# Voltage_Measurement.net
KiCad netlist of a schematic drawn in Altium Designer
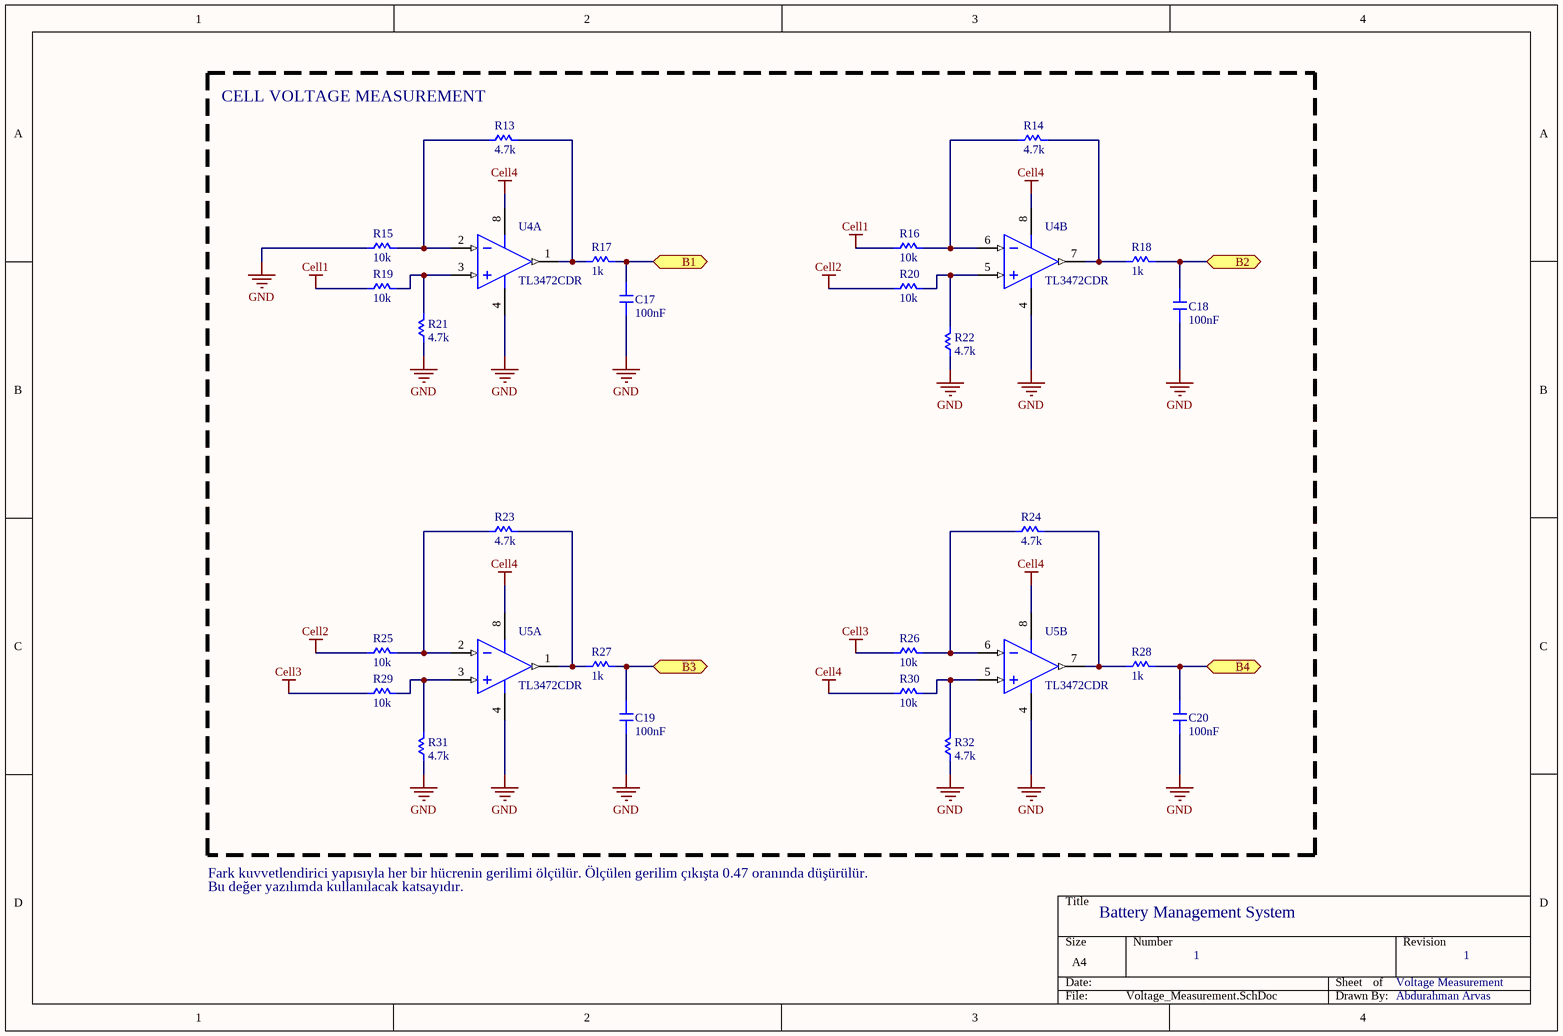
[diagram p0: Voltage_Measurement.SchDoc]

(export (version "E")
  (design (tool "Eeschema 10.0.6"))
  (components
    (comp (ref "C17")
      (value "100nF")
      (footprint "C0805")
      (libsource (lib "Arvas_AltiumSCH") (part "SMD_Capacitor"))
    )
    (comp (ref "C18")
      (value "100nF")
      (footprint "C0805")
      (libsource (lib "Arvas_AltiumSCH") (part "SMD_Capacitor"))
    )
    (comp (ref "C19")
      (value "100nF")
      (footprint "C0805")
      (libsource (lib "Arvas_AltiumSCH") (part "SMD_Capacitor"))
    )
    (comp (ref "C20")
      (value "100nF")
      (footprint "C0805")
      (libsource (lib "Arvas_AltiumSCH") (part "SMD_Capacitor"))
    )
    (comp (ref "R13")
      (value "4.7k")
      (footprint "R0805")
      (description "SMD Chip Resistor")
      (libsource (lib "Arvas_AltiumSCH") (part "SMD Resistor"))
    )
    (comp (ref "R14")
      (value "4.7k")
      (footprint "R0805")
      (description "SMD Chip Resistor")
      (libsource (lib "Arvas_AltiumSCH") (part "SMD Resistor"))
    )
    (comp (ref "R15")
      (value "10k")
      (footprint "R0805")
      (description "SMD Chip Resistor")
      (libsource (lib "Arvas_AltiumSCH") (part "SMD Resistor"))
    )
    (comp (ref "R16")
      (value "10k")
      (footprint "R0805")
      (description "SMD Chip Resistor")
      (libsource (lib "Arvas_AltiumSCH") (part "SMD Resistor"))
    )
    (comp (ref "R17")
      (value "1k")
      (footprint "R0805")
      (description "SMD Chip Resistor")
      (libsource (lib "Arvas_AltiumSCH") (part "SMD Resistor"))
    )
    (comp (ref "R18")
      (value "1k")
      (footprint "R0805")
      (description "SMD Chip Resistor")
      (libsource (lib "Arvas_AltiumSCH") (part "SMD Resistor"))
    )
    (comp (ref "R19")
      (value "10k")
      (footprint "R0805")
      (description "SMD Chip Resistor")
      (libsource (lib "Arvas_AltiumSCH") (part "SMD Resistor"))
    )
    (comp (ref "R20")
      (value "10k")
      (footprint "R0805")
      (description "SMD Chip Resistor")
      (libsource (lib "Arvas_AltiumSCH") (part "SMD Resistor"))
    )
    (comp (ref "R21")
      (value "4.7k")
      (footprint "R0805")
      (description "SMD Chip Resistor")
      (libsource (lib "Arvas_AltiumSCH") (part "SMD Resistor"))
    )
    (comp (ref "R22")
      (value "4.7k")
      (footprint "R0805")
      (description "SMD Chip Resistor")
      (libsource (lib "Arvas_AltiumSCH") (part "SMD Resistor"))
    )
    (comp (ref "R23")
      (value "4.7k")
      (footprint "R0805")
      (description "SMD Chip Resistor")
      (libsource (lib "Arvas_AltiumSCH") (part "SMD Resistor"))
    )
    (comp (ref "R24")
      (value "4.7k")
      (footprint "R0805")
      (description "SMD Chip Resistor")
      (libsource (lib "Arvas_AltiumSCH") (part "SMD Resistor"))
    )
    (comp (ref "R25")
      (value "10k")
      (footprint "R0805")
      (description "SMD Chip Resistor")
      (libsource (lib "Arvas_AltiumSCH") (part "SMD Resistor"))
    )
    (comp (ref "R26")
      (value "10k")
      (footprint "R0805")
      (description "SMD Chip Resistor")
      (libsource (lib "Arvas_AltiumSCH") (part "SMD Resistor"))
    )
    (comp (ref "R27")
      (value "1k")
      (footprint "R0805")
      (description "SMD Chip Resistor")
      (libsource (lib "Arvas_AltiumSCH") (part "SMD Resistor"))
    )
    (comp (ref "R28")
      (value "1k")
      (footprint "R0805")
      (description "SMD Chip Resistor")
      (libsource (lib "Arvas_AltiumSCH") (part "SMD Resistor"))
    )
    (comp (ref "R29")
      (value "10k")
      (footprint "R0805")
      (description "SMD Chip Resistor")
      (libsource (lib "Arvas_AltiumSCH") (part "SMD Resistor"))
    )
    (comp (ref "R30")
      (value "10k")
      (footprint "R0805")
      (description "SMD Chip Resistor")
      (libsource (lib "Arvas_AltiumSCH") (part "SMD Resistor"))
    )
    (comp (ref "R31")
      (value "4.7k")
      (footprint "R0805")
      (description "SMD Chip Resistor")
      (libsource (lib "Arvas_AltiumSCH") (part "SMD Resistor"))
    )
    (comp (ref "R32")
      (value "4.7k")
      (footprint "R0805")
      (description "SMD Chip Resistor")
      (libsource (lib "Arvas_AltiumSCH") (part "SMD Resistor"))
    )
    (comp (ref "U4")
      (value "TL3472CDR")
      (footprint "D0008A_L")
      (fields (field (name "MANUFACTURER") "Texas Instruments"))
      (libsource (lib "Altium Content Vault") (part "TI-TL3472-XX-X8"))
    )
    (comp (ref "U5")
      (value "TL3472CDR")
      (footprint "D0008A_L")
      (fields (field (name "MANUFACTURER") "Texas Instruments"))
      (libsource (lib "Altium Content Vault") (part "TI-TL3472-XX-X8"))
    )
  )
  (nets
    (net (code "1") (name "/B1") (class "Default")
      (node (ref "C17") (pin "2") (pinfunction "2_2") (pintype "passive"))
      (node (ref "R17") (pin "2") (pinfunction "2_2") (pintype "passive"))
    )
    (net (code "2") (name "/B2") (class "Default")
      (node (ref "C18") (pin "2") (pinfunction "2_2") (pintype "passive"))
      (node (ref "R18") (pin "2") (pinfunction "2_2") (pintype "passive"))
    )
    (net (code "3") (name "/B3") (class "Default")
      (node (ref "C19") (pin "2") (pinfunction "2_2") (pintype "passive"))
      (node (ref "R27") (pin "2") (pinfunction "2_2") (pintype "passive"))
    )
    (net (code "4") (name "/B4") (class "Default")
      (node (ref "C20") (pin "2") (pinfunction "2_2") (pintype "passive"))
      (node (ref "R28") (pin "2") (pinfunction "2_2") (pintype "passive"))
    )
    (net (code "5") (name "Cell1") (class "Default")
      (node (ref "R16") (pin "1") (pinfunction "1_1") (pintype "passive"))
      (node (ref "R19") (pin "1") (pinfunction "1_1") (pintype "passive"))
    )
    (net (code "6") (name "Cell2") (class "Default")
      (node (ref "R20") (pin "1") (pinfunction "1_1") (pintype "passive"))
      (node (ref "R25") (pin "1") (pinfunction "1_1") (pintype "passive"))
    )
    (net (code "7") (name "Cell3") (class "Default")
      (node (ref "R26") (pin "1") (pinfunction "1_1") (pintype "passive"))
      (node (ref "R29") (pin "1") (pinfunction "1_1") (pintype "passive"))
    )
    (net (code "8") (name "Cell4") (class "Default")
      (node (ref "R30") (pin "1") (pinfunction "1_1") (pintype "passive"))
      (node (ref "U4") (pin "8") (pinfunction "VCC+_8") (pintype "power_in"))
      (node (ref "U5") (pin "8") (pinfunction "VCC+_8") (pintype "power_in"))
    )
    (net (code "9") (name "GND") (class "Default")
      (node (ref "C17") (pin "1") (pinfunction "1_1") (pintype "passive"))
      (node (ref "C18") (pin "1") (pinfunction "1_1") (pintype "passive"))
      (node (ref "C19") (pin "1") (pinfunction "1_1") (pintype "passive"))
      (node (ref "C20") (pin "1") (pinfunction "1_1") (pintype "passive"))
      (node (ref "R15") (pin "1") (pinfunction "1_1") (pintype "passive"))
      (node (ref "R21") (pin "1") (pinfunction "1_1") (pintype "passive"))
      (node (ref "R22") (pin "1") (pinfunction "1_1") (pintype "passive"))
      (node (ref "R31") (pin "1") (pinfunction "1_1") (pintype "passive"))
      (node (ref "R32") (pin "1") (pinfunction "1_1") (pintype "passive"))
      (node (ref "U4") (pin "4") (pinfunction "VCC-/GND_4") (pintype "power_in"))
      (node (ref "U5") (pin "4") (pinfunction "VCC-/GND_4") (pintype "power_in"))
    )
    (net (code "10") (name "Net-(U4A-IN1+)") (class "Default")
      (node (ref "R19") (pin "2") (pinfunction "2_2") (pintype "passive"))
      (node (ref "R21") (pin "2") (pinfunction "2_2") (pintype "passive"))
      (node (ref "U4") (pin "3") (pinfunction "IN1+_3") (pintype "input"))
    )
    (net (code "11") (name "Net-(U4A-IN1-)") (class "Default")
      (node (ref "R13") (pin "1") (pinfunction "1_1") (pintype "passive"))
      (node (ref "R15") (pin "2") (pinfunction "2_2") (pintype "passive"))
      (node (ref "U4") (pin "2") (pinfunction "IN1-_2") (pintype "input"))
    )
    (net (code "12") (name "Net-(U4A-OUT1)") (class "Default")
      (node (ref "R13") (pin "2") (pinfunction "2_2") (pintype "passive"))
      (node (ref "R17") (pin "1") (pinfunction "1_1") (pintype "passive"))
      (node (ref "U4") (pin "1") (pinfunction "OUT1_1") (pintype "output"))
    )
    (net (code "13") (name "Net-(U4B-IN2+)") (class "Default")
      (node (ref "R20") (pin "2") (pinfunction "2_2") (pintype "passive"))
      (node (ref "R22") (pin "2") (pinfunction "2_2") (pintype "passive"))
      (node (ref "U4") (pin "5") (pinfunction "IN2+_5") (pintype "input"))
    )
    (net (code "14") (name "Net-(U4B-IN2-)") (class "Default")
      (node (ref "R14") (pin "1") (pinfunction "1_1") (pintype "passive"))
      (node (ref "R16") (pin "2") (pinfunction "2_2") (pintype "passive"))
      (node (ref "U4") (pin "6") (pinfunction "IN2-_6") (pintype "input"))
    )
    (net (code "15") (name "Net-(U4B-OUT2)") (class "Default")
      (node (ref "R14") (pin "2") (pinfunction "2_2") (pintype "passive"))
      (node (ref "R18") (pin "1") (pinfunction "1_1") (pintype "passive"))
      (node (ref "U4") (pin "7") (pinfunction "OUT2_7") (pintype "output"))
    )
    (net (code "16") (name "Net-(U5A-IN1+)") (class "Default")
      (node (ref "R29") (pin "2") (pinfunction "2_2") (pintype "passive"))
      (node (ref "R31") (pin "2") (pinfunction "2_2") (pintype "passive"))
      (node (ref "U5") (pin "3") (pinfunction "IN1+_3") (pintype "input"))
    )
    (net (code "17") (name "Net-(U5A-IN1-)") (class "Default")
      (node (ref "R23") (pin "1") (pinfunction "1_1") (pintype "passive"))
      (node (ref "R25") (pin "2") (pinfunction "2_2") (pintype "passive"))
      (node (ref "U5") (pin "2") (pinfunction "IN1-_2") (pintype "input"))
    )
    (net (code "18") (name "Net-(U5A-OUT1)") (class "Default")
      (node (ref "R23") (pin "2") (pinfunction "2_2") (pintype "passive"))
      (node (ref "R27") (pin "1") (pinfunction "1_1") (pintype "passive"))
      (node (ref "U5") (pin "1") (pinfunction "OUT1_1") (pintype "output"))
    )
    (net (code "19") (name "Net-(U5B-IN2+)") (class "Default")
      (node (ref "R30") (pin "2") (pinfunction "2_2") (pintype "passive"))
      (node (ref "R32") (pin "2") (pinfunction "2_2") (pintype "passive"))
      (node (ref "U5") (pin "5") (pinfunction "IN2+_5") (pintype "input"))
    )
    (net (code "20") (name "Net-(U5B-IN2-)") (class "Default")
      (node (ref "R24") (pin "1") (pinfunction "1_1") (pintype "passive"))
      (node (ref "R26") (pin "2") (pinfunction "2_2") (pintype "passive"))
      (node (ref "U5") (pin "6") (pinfunction "IN2-_6") (pintype "input"))
    )
    (net (code "21") (name "Net-(U5B-OUT2)") (class "Default")
      (node (ref "R24") (pin "2") (pinfunction "2_2") (pintype "passive"))
      (node (ref "R28") (pin "1") (pinfunction "1_1") (pintype "passive"))
      (node (ref "U5") (pin "7") (pinfunction "OUT2_7") (pintype "output"))
    )
  )
)
